# NICK_REEAL_SCHEMATIC.net
KiCad netlist of a schematic drawn in EAGLE
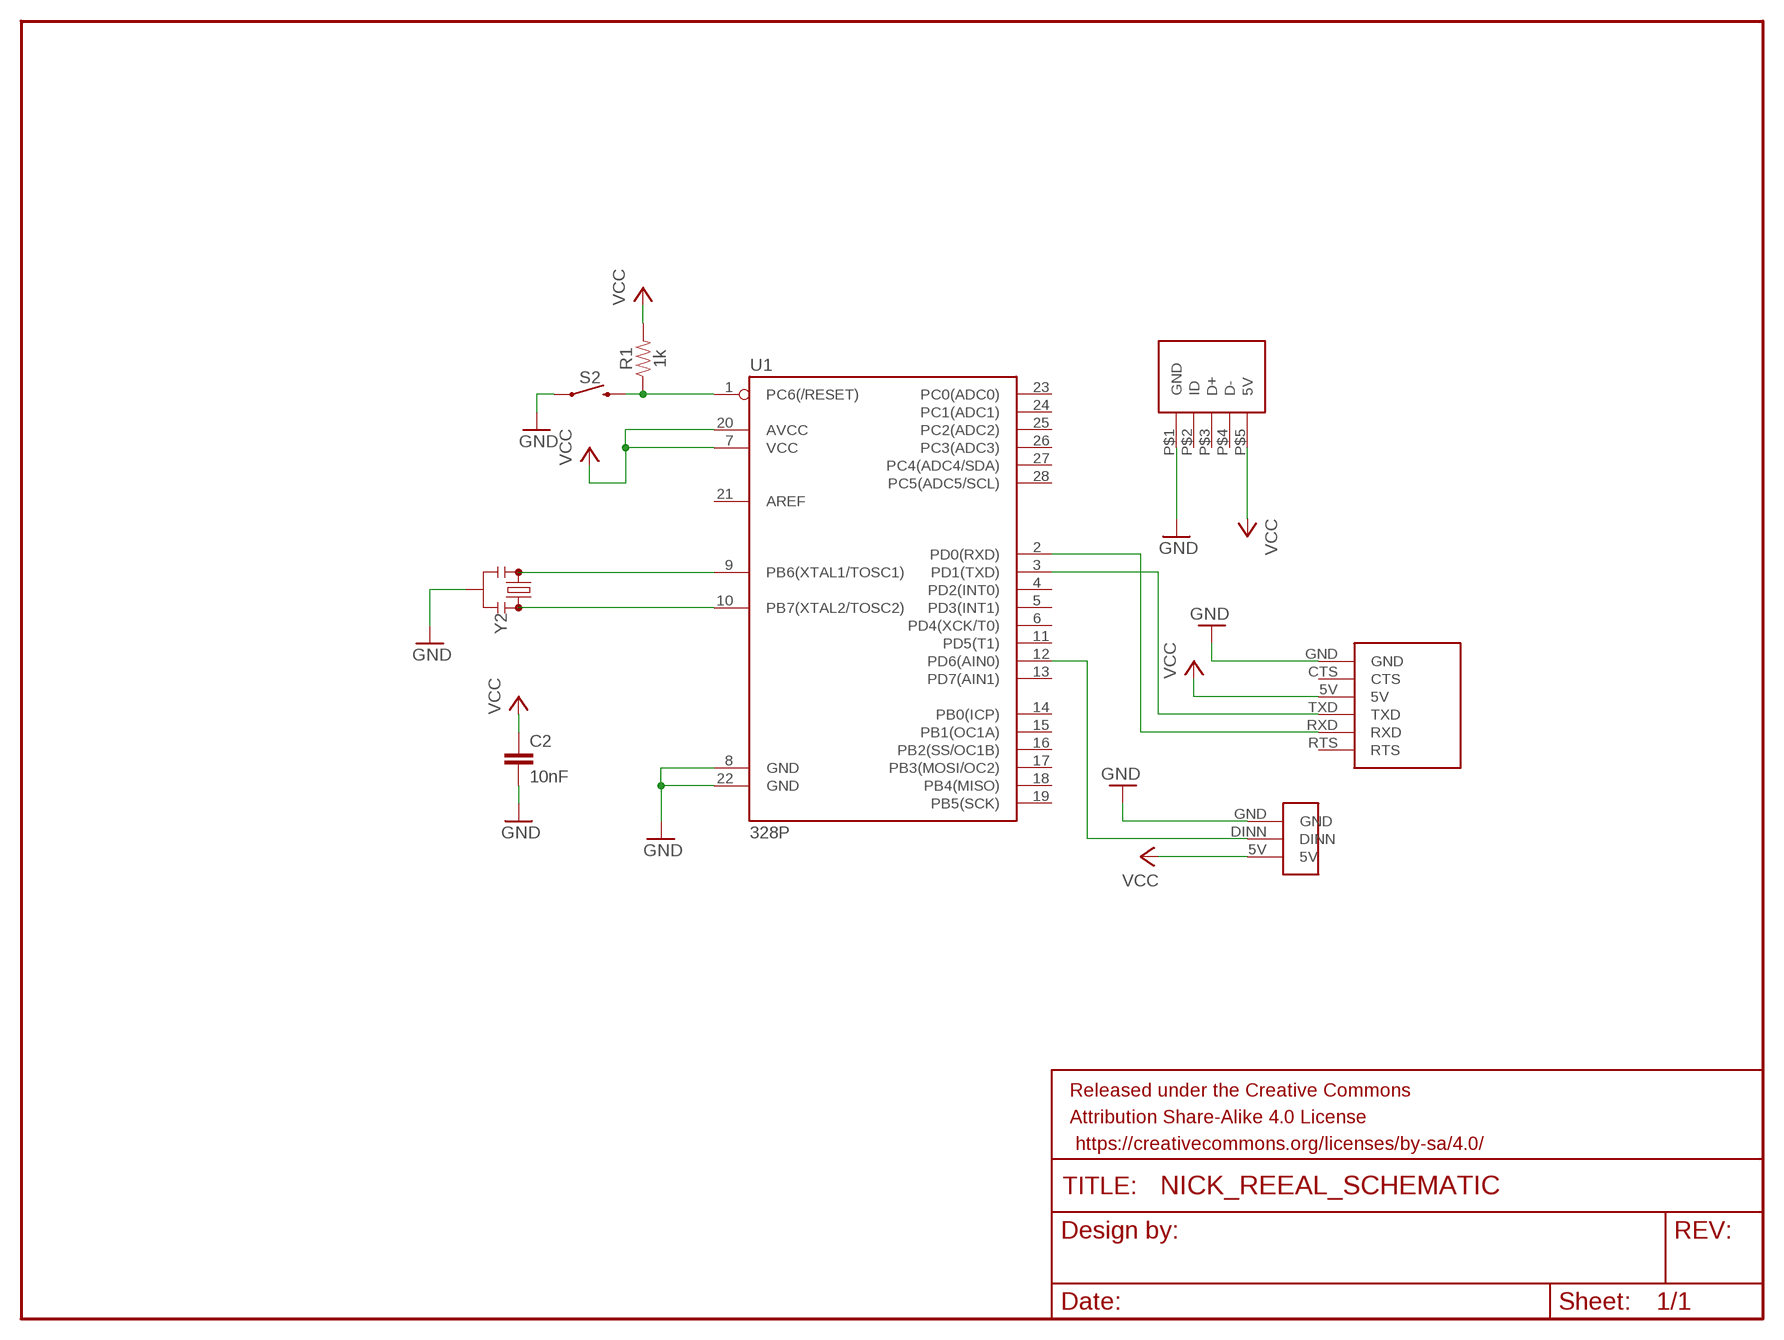
[diagram p0: schematic, sheet 1]

(export (version "E")
  (design (tool "Eeschema 10.0.6"))
  (components
    (comp (ref "C2")
      (value "10nF")
      (footprint "eagle-import:CAP-PTH-10MM")
      (libsource (lib "eagle-import") (part "10NF-PTH-10MM-10000V-1-%"))
    )
    (comp (ref "FRAME1")
      (value "FRAME-LETTERNO_PACKAGE")
      (footprint "eagle-import:DUMMY")
      (fields (field (name "DESIGNER") "Nobody"))
      (libsource (lib "eagle-import") (part "FRAME-LETTERNO_PACKAGE"))
    )
    (comp (ref "R1")
      (value "1k")
      (footprint "eagle-import:AXIAL-0.3")
      (libsource (lib "eagle-import") (part "1KOHM-HORIZ-1/4W-1%"))
    )
    (comp (ref "S2")
      (value "MOMENTARY-SWITCH-SPST-PTH-6.0MM")
      (footprint "eagle-import:TACTILE_SWITCH_PTH_6.0MM")
      (libsource (lib "eagle-import") (part "MOMENTARY-SWITCH-SPST-PTH-6.0MM"))
    )
    (comp (ref "U$1")
      (value "USBCONNECTER")
      (footprint "eagle-import:USBCONNECTER")
      (libsource (lib "eagle-import") (part "USBCONNECTER"))
    )
    (comp (ref "U$2")
      (value "PROGRAMCABLE")
      (footprint "eagle-import:PROGRAMCABLE")
      (libsource (lib "eagle-import") (part "PROGRAMCABLE"))
    )
    (comp (ref "U$3")
      (value "8LEDCONNECTER")
      (footprint "eagle-import:8LEDCONNECTER")
      (libsource (lib "eagle-import") (part "8LEDCONNECTER"))
    )
    (comp (ref "U1")
      (value "328P")
      (footprint "eagle-import:DIP28")
      (libsource (lib "eagle-import") (part "ATMEGA328P_PDIP"))
    )
    (comp (ref "Y2")
      (value "RESONATORPTH-7.6X3.8")
      (footprint "eagle-import:RESONATOR-PTH-7.6X3.8")
      (libsource (lib "eagle-import") (part "RESONATORPTH-7.6X3.8"))
    )
  )
  (nets
    (net (code "1") (name "GND") (class "Default")
      (node (ref "C2") (pin "2") (pinfunction "2_2") (pintype "passive"))
      (node (ref "S2") (pin "1") (pinfunction "1_1") (pintype "passive"))
      (node (ref "U$1") (pin "P$1") (pinfunction "GND_P$1") (pintype "bidirectional"))
      (node (ref "U$2") (pin "GND") (pinfunction "GND_GND") (pintype "bidirectional"))
      (node (ref "U$3") (pin "GND") (pinfunction "GND_GND") (pintype "bidirectional"))
      (node (ref "U1") (pin "22") (pinfunction "GND_22") (pintype "bidirectional"))
      (node (ref "U1") (pin "8") (pinfunction "GND_8") (pintype "bidirectional"))
      (node (ref "Y2") (pin "2") (pinfunction "2_2") (pintype "passive"))
    )
    (net (code "2") (name "Net-(R1-1)") (class "Default")
      (node (ref "R1") (pin "P$1") (pinfunction "1_P$1") (pintype "passive"))
      (node (ref "S2") (pin "3") (pinfunction "2_3") (pintype "passive"))
      (node (ref "U1") (pin "1") (pinfunction "PC6(/RESET)_1") (pintype "bidirectional"))
    )
    (net (code "3") (name "Net-(U1-PB6(XTAL1{slash}TOSC1))") (class "Default")
      (node (ref "U1") (pin "9") (pinfunction "PB6(XTAL1/TOSC1)_9") (pintype "bidirectional"))
      (node (ref "Y2") (pin "3") (pinfunction "3_3") (pintype "passive"))
    )
    (net (code "4") (name "Net-(U1-PB7(XTAL2{slash}TOSC2))") (class "Default")
      (node (ref "U1") (pin "10") (pinfunction "PB7(XTAL2/TOSC2)_10") (pintype "bidirectional"))
      (node (ref "Y2") (pin "1") (pinfunction "1_1") (pintype "passive"))
    )
    (net (code "5") (name "Net-(U1-PD0(RXD))") (class "Default")
      (node (ref "U$2") (pin "RXD") (pinfunction "RXD_RXD") (pintype "bidirectional"))
      (node (ref "U1") (pin "2") (pinfunction "PD0(RXD)_2") (pintype "bidirectional"))
    )
    (net (code "6") (name "Net-(U1-PD1(TXD))") (class "Default")
      (node (ref "U$2") (pin "TXD") (pinfunction "TXD_TXD") (pintype "bidirectional"))
      (node (ref "U1") (pin "3") (pinfunction "PD1(TXD)_3") (pintype "bidirectional"))
    )
    (net (code "7") (name "Net-(U1-PD6(AIN0))") (class "Default")
      (node (ref "U$3") (pin "DINN") (pinfunction "DINN_DINN") (pintype "bidirectional"))
      (node (ref "U1") (pin "12") (pinfunction "PD6(AIN0)_12") (pintype "bidirectional"))
    )
    (net (code "8") (name "VCC") (class "Default")
      (node (ref "C2") (pin "1") (pinfunction "1_1") (pintype "passive"))
      (node (ref "R1") (pin "P$2") (pinfunction "2_P$2") (pintype "passive"))
      (node (ref "U$1") (pin "P$5") (pinfunction "5V_P$5") (pintype "bidirectional"))
      (node (ref "U$2") (pin "5V") (pinfunction "5V_5V") (pintype "bidirectional"))
      (node (ref "U$3") (pin "5V") (pinfunction "5V_5V") (pintype "bidirectional"))
      (node (ref "U1") (pin "20") (pinfunction "AVCC_20") (pintype "bidirectional"))
      (node (ref "U1") (pin "7") (pinfunction "VCC_7") (pintype "bidirectional"))
    )
    (net (code "9") (name "unconnected-(U$1-D+-PadP$3)") (class "Default")
      (node (ref "U$1") (pin "P$3") (pinfunction "D+_P$3") (pintype "bidirectional"))
    )
    (net (code "10") (name "unconnected-(U$1-D--PadP$4)") (class "Default")
      (node (ref "U$1") (pin "P$4") (pinfunction "D-_P$4") (pintype "bidirectional"))
    )
    (net (code "11") (name "unconnected-(U$1-ID-PadP$2)") (class "Default")
      (node (ref "U$1") (pin "P$2") (pinfunction "ID_P$2") (pintype "bidirectional"))
    )
    (net (code "12") (name "unconnected-(U$2-PadCTS)") (class "Default")
      (node (ref "U$2") (pin "CTS") (pinfunction "CTS_CTS") (pintype "bidirectional"))
    )
    (net (code "13") (name "unconnected-(U$2-PadRTS)") (class "Default")
      (node (ref "U$2") (pin "RTS") (pinfunction "RTS_RTS") (pintype "bidirectional"))
    )
    (net (code "14") (name "unconnected-(U1-AREF-Pad21)") (class "Default")
      (node (ref "U1") (pin "21") (pinfunction "AREF_21") (pintype "bidirectional"))
    )
    (net (code "15") (name "unconnected-(U1-PB0(ICP)-Pad14)") (class "Default")
      (node (ref "U1") (pin "14") (pinfunction "PB0(ICP)_14") (pintype "bidirectional"))
    )
    (net (code "16") (name "unconnected-(U1-PB1(OC1A)-Pad15)") (class "Default")
      (node (ref "U1") (pin "15") (pinfunction "PB1(OC1A)_15") (pintype "bidirectional"))
    )
    (net (code "17") (name "unconnected-(U1-PB2(SS{slash}OC1B)-Pad16)") (class "Default")
      (node (ref "U1") (pin "16") (pinfunction "PB2(SS/OC1B)_16") (pintype "bidirectional"))
    )
    (net (code "18") (name "unconnected-(U1-PB3(MOSI{slash}OC2)-Pad17)") (class "Default")
      (node (ref "U1") (pin "17") (pinfunction "PB3(MOSI/OC2)_17") (pintype "bidirectional"))
    )
    (net (code "19") (name "unconnected-(U1-PB4(MISO)-Pad18)") (class "Default")
      (node (ref "U1") (pin "18") (pinfunction "PB4(MISO)_18") (pintype "bidirectional"))
    )
    (net (code "20") (name "unconnected-(U1-PB5(SCK)-Pad19)") (class "Default")
      (node (ref "U1") (pin "19") (pinfunction "PB5(SCK)_19") (pintype "bidirectional"))
    )
    (net (code "21") (name "unconnected-(U1-PC0(ADC0)-Pad23)") (class "Default")
      (node (ref "U1") (pin "23") (pinfunction "PC0(ADC0)_23") (pintype "bidirectional"))
    )
    (net (code "22") (name "unconnected-(U1-PC1(ADC1)-Pad24)") (class "Default")
      (node (ref "U1") (pin "24") (pinfunction "PC1(ADC1)_24") (pintype "bidirectional"))
    )
    (net (code "23") (name "unconnected-(U1-PC2(ADC2)-Pad25)") (class "Default")
      (node (ref "U1") (pin "25") (pinfunction "PC2(ADC2)_25") (pintype "bidirectional"))
    )
    (net (code "24") (name "unconnected-(U1-PC3(ADC3)-Pad26)") (class "Default")
      (node (ref "U1") (pin "26") (pinfunction "PC3(ADC3)_26") (pintype "bidirectional"))
    )
    (net (code "25") (name "unconnected-(U1-PC4(ADC4{slash}SDA)-Pad27)") (class "Default")
      (node (ref "U1") (pin "27") (pinfunction "PC4(ADC4/SDA)_27") (pintype "bidirectional"))
    )
    (net (code "26") (name "unconnected-(U1-PC5(ADC5{slash}SCL)-Pad28)") (class "Default")
      (node (ref "U1") (pin "28") (pinfunction "PC5(ADC5/SCL)_28") (pintype "bidirectional"))
    )
    (net (code "27") (name "unconnected-(U1-PD2(INT0)-Pad4)") (class "Default")
      (node (ref "U1") (pin "4") (pinfunction "PD2(INT0)_4") (pintype "bidirectional"))
    )
    (net (code "28") (name "unconnected-(U1-PD3(INT1)-Pad5)") (class "Default")
      (node (ref "U1") (pin "5") (pinfunction "PD3(INT1)_5") (pintype "bidirectional"))
    )
    (net (code "29") (name "unconnected-(U1-PD4(XCK{slash}T0)-Pad6)") (class "Default")
      (node (ref "U1") (pin "6") (pinfunction "PD4(XCK/T0)_6") (pintype "bidirectional"))
    )
    (net (code "30") (name "unconnected-(U1-PD5(T1)-Pad11)") (class "Default")
      (node (ref "U1") (pin "11") (pinfunction "PD5(T1)_11") (pintype "bidirectional"))
    )
    (net (code "31") (name "unconnected-(U1-PD7(AIN1)-Pad13)") (class "Default")
      (node (ref "U1") (pin "13") (pinfunction "PD7(AIN1)_13") (pintype "bidirectional"))
    )
  )
)
